# 1_0.net
KiCad netlist of a schematic drawn in Altium Designer
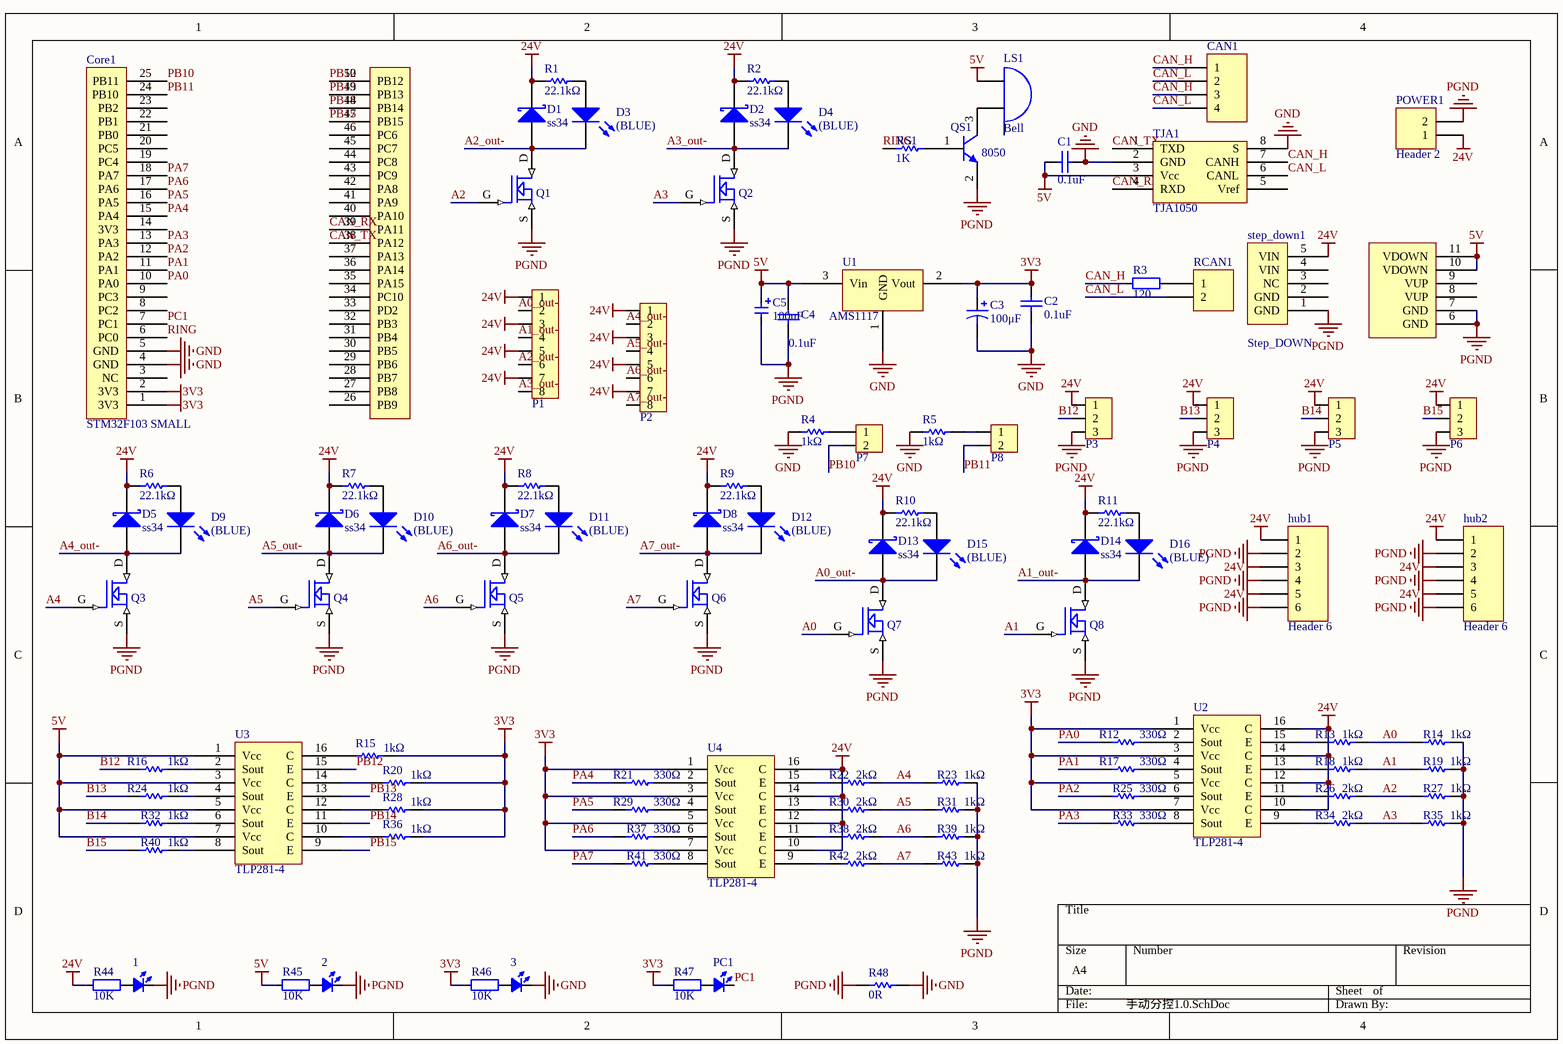
[diagram p0: 手动分控1.0.SchDoc]

(export (version "E")
  (design (tool "Eeschema 10.0.6"))
  (components
    (comp (ref "1")
      (value "LED_0603")
      (footprint "LED_0805_GREEN")
      (description "LED")
      (libsource (lib "Integrated_Library") (part "LED_0603"))
    )
    (comp (ref "2")
      (value "LED_0603")
      (footprint "LED_0805_GREEN")
      (description "LED")
      (libsource (lib "Integrated_Library") (part "LED_0603"))
    )
    (comp (ref "3")
      (value "LED_0603")
      (footprint "LED_0805_GREEN")
      (description "LED")
      (libsource (lib "Integrated_Library") (part "LED_0603"))
    )
    (comp (ref "C1")
      (value "0.1uF")
      (footprint "CAP-MLCC-0603")
      (description "Capacitor")
      (fields (field (name "Comment") "Cap") (field (name "PUBLISHER") "Altium Limited"))
      (libsource (lib "K60-mainboard-v3.1") (part "Cap"))
    )
    (comp (ref "C2")
      (value "0.1uF")
      (footprint "CAP-MLCC-0603")
      (description "Capacitor")
      (fields (field (name "Comment") "Cap") (field (name "PUBLISHER") "Altium Limited"))
      (libsource (lib "K60-mainboard-v3.1") (part "Cap"))
    )
    (comp (ref "C3")
      (value "100μF")
      (footprint "CAP-TAN-3216/CAPA")
      (description "钽电容")
      (fields (field (name "PUBLISHER") "Altium Limited"))
      (libsource (lib "Libraries_2014_0618") (part "CAP-TAN"))
    )
    (comp (ref "C4")
      (value "0.1uF")
      (footprint "CAP-MLCC-0603")
      (description "Capacitor")
      (fields (field (name "Comment") "Cap") (field (name "PUBLISHER") "Altium Limited"))
      (libsource (lib "K60-mainboard-v3.1") (part "Cap"))
    )
    (comp (ref "C5")
      (value "100uF")
      (footprint "CAP-TAN-6032/CAPC")
      (description "Capacitor")
      (fields (field (name "Comment") "Cap_Tan_0805"))
      (libsource (lib "Integrated_Library") (part "Cap_Tan_0805"))
    )
    (comp (ref "CAN1")
      (value "Header 4")
      (footprint "Green_4P")
      (description "Header, 4-Pin")
      (fields (field (name "PUBLISHER") "Altium Limited"))
      (libsource (lib "Libraries_2014_0618") (part "Header 4"))
    )
    (comp (ref "Core1")
      (value "STM32F103 SMALL")
      (footprint "STM32F103Small")
      (libsource (lib "K60-mainboard-v3.1") (part "STM32F103 SMALL"))
    )
    (comp (ref "D1")
      (value "ss34")
      (footprint "ss34")
      (description "肖特基二极管")
      (fields (field (name "PUBLISHER") "Altium Limited"))
      (libsource (lib "Libraries_2014_0618") (part "DIODE-Schottky"))
    )
    (comp (ref "D2")
      (value "ss34")
      (footprint "ss34")
      (description "肖特基二极管")
      (fields (field (name "PUBLISHER") "Altium Limited"))
      (libsource (lib "Libraries_2014_0618") (part "DIODE-Schottky"))
    )
    (comp (ref "D3")
      (value "(BLUE)")
      (footprint "LED-0805")
      (description "LED")
      (fields (field (name "PUBLISHER") "Altium Limited"))
      (libsource (lib "Libraries_2014_0618") (part "LED"))
    )
    (comp (ref "D4")
      (value "(BLUE)")
      (footprint "LED-0805")
      (description "LED")
      (fields (field (name "PUBLISHER") "Altium Limited"))
      (libsource (lib "Libraries_2014_0618") (part "LED"))
    )
    (comp (ref "D5")
      (value "ss34")
      (footprint "ss34")
      (description "肖特基二极管")
      (fields (field (name "PUBLISHER") "Altium Limited"))
      (libsource (lib "Libraries_2014_0618") (part "DIODE-Schottky"))
    )
    (comp (ref "D6")
      (value "ss34")
      (footprint "ss34")
      (description "肖特基二极管")
      (fields (field (name "PUBLISHER") "Altium Limited"))
      (libsource (lib "Libraries_2014_0618") (part "DIODE-Schottky"))
    )
    (comp (ref "D7")
      (value "ss34")
      (footprint "ss34")
      (description "肖特基二极管")
      (fields (field (name "PUBLISHER") "Altium Limited"))
      (libsource (lib "Libraries_2014_0618") (part "DIODE-Schottky"))
    )
    (comp (ref "D8")
      (value "ss34")
      (footprint "ss34")
      (description "肖特基二极管")
      (fields (field (name "PUBLISHER") "Altium Limited"))
      (libsource (lib "Libraries_2014_0618") (part "DIODE-Schottky"))
    )
    (comp (ref "D9")
      (value "(BLUE)")
      (footprint "LED-0805")
      (description "LED")
      (fields (field (name "PUBLISHER") "Altium Limited"))
      (libsource (lib "Libraries_2014_0618") (part "LED"))
    )
    (comp (ref "D10")
      (value "(BLUE)")
      (footprint "LED-0805")
      (description "LED")
      (fields (field (name "PUBLISHER") "Altium Limited"))
      (libsource (lib "Libraries_2014_0618") (part "LED"))
    )
    (comp (ref "D11")
      (value "(BLUE)")
      (footprint "LED-0805")
      (description "LED")
      (fields (field (name "PUBLISHER") "Altium Limited"))
      (libsource (lib "Libraries_2014_0618") (part "LED"))
    )
    (comp (ref "D12")
      (value "(BLUE)")
      (footprint "LED-0805")
      (description "LED")
      (fields (field (name "PUBLISHER") "Altium Limited"))
      (libsource (lib "Libraries_2014_0618") (part "LED"))
    )
    (comp (ref "D13")
      (value "ss34")
      (footprint "ss34")
      (description "肖特基二极管")
      (fields (field (name "PUBLISHER") "Altium Limited"))
      (libsource (lib "Libraries_2014_0618") (part "DIODE-Schottky"))
    )
    (comp (ref "D14")
      (value "ss34")
      (footprint "ss34")
      (description "肖特基二极管")
      (fields (field (name "PUBLISHER") "Altium Limited"))
      (libsource (lib "Libraries_2014_0618") (part "DIODE-Schottky"))
    )
    (comp (ref "D15")
      (value "(BLUE)")
      (footprint "LED-0805")
      (description "LED")
      (fields (field (name "PUBLISHER") "Altium Limited"))
      (libsource (lib "Libraries_2014_0618") (part "LED"))
    )
    (comp (ref "D16")
      (value "(BLUE)")
      (footprint "LED-0805")
      (description "LED")
      (fields (field (name "PUBLISHER") "Altium Limited"))
      (libsource (lib "Libraries_2014_0618") (part "LED"))
    )
    (comp (ref "hub1")
      (value "Header 6")
      (footprint "Green_6P")
      (description "Header, 6-Pin")
      (fields (field (name "PUBLISHER") "Altium Limited"))
      (libsource (lib "Libraries_2014_0618") (part "Header 6"))
    )
    (comp (ref "hub2")
      (value "Header 6")
      (footprint "Green_6P")
      (description "Header, 6-Pin")
      (fields (field (name "PUBLISHER") "Altium Limited"))
      (libsource (lib "Libraries_2014_0618") (part "Header 6"))
    )
    (comp (ref "LS1")
      (value "Bell")
      (footprint "CAP-ELE-PIN200/DIA250")
      (description "Electrical Bell")
      (fields (field (name "PUBLISHER") "Altium Limited"))
      (libsource (lib "Miscellaneous Devices") (part "Bell"))
    )
    (comp (ref "P1")
      (value "HDR1x8_1.27")
      (footprint "HDR1X8_1.27_180")
      (description "Header")
      (libsource (lib "Integrated_Library") (part "HDR1x8_1.27"))
    )
    (comp (ref "P2")
      (value "HDR1x8_1.27")
      (footprint "HDR1X8_1.27_180")
      (description "Header")
      (libsource (lib "Integrated_Library") (part "HDR1x8_1.27"))
    )
    (comp (ref "P3")
      (value "HDR1x3_2.54")
      (footprint "Green_3P")
      (description "Header")
      (libsource (lib "Integrated_Library") (part "HDR1x3_2.54"))
    )
    (comp (ref "P4")
      (value "HDR1x3_2.54")
      (footprint "Green_3P")
      (description "Header")
      (libsource (lib "Integrated_Library") (part "HDR1x3_2.54"))
    )
    (comp (ref "P5")
      (value "HDR1x3_2.54")
      (footprint "Green_3P")
      (description "Header")
      (libsource (lib "Integrated_Library") (part "HDR1x3_2.54"))
    )
    (comp (ref "P6")
      (value "HDR1x3_2.54")
      (footprint "Green_3P")
      (description "Header")
      (libsource (lib "Integrated_Library") (part "HDR1x3_2.54"))
    )
    (comp (ref "P7")
      (value "HDR1x2_2.54")
      (footprint "Green_2P")
      (description "Header")
      (libsource (lib "Integrated_Library") (part "HDR1x2_2.54"))
    )
    (comp (ref "P8")
      (value "HDR1x2_2.54")
      (footprint "Green_2P")
      (description "Header")
      (libsource (lib "Integrated_Library") (part "HDR1x2_2.54"))
    )
    (comp (ref "PC1")
      (value "LED_0603")
      (footprint "LED_0805_GREEN")
      (description "LED")
      (libsource (lib "Integrated_Library") (part "LED_0603"))
    )
    (comp (ref "POWER1")
      (value "Header 2")
      (footprint "Green_2P")
      (description "Header, 2-Pin")
      (fields (field (name "PUBLISHER") "Altium Limited"))
      (libsource (lib "K60-mainboard-v3.1") (part "Header 2"))
    )
    (comp (ref "Q1")
      (value "MOSFET N")
      (footprint "NMOS_SOT23")
      (description "IRF530")
      (libsource (lib "K60-mainboard-v3.1") (part "MOSFET N"))
    )
    (comp (ref "Q2")
      (value "MOSFET N")
      (footprint "NMOS_SOT23")
      (description "IRF530")
      (libsource (lib "K60-mainboard-v3.1") (part "MOSFET N"))
    )
    (comp (ref "Q3")
      (value "MOSFET N")
      (footprint "NMOS_SOT23")
      (description "IRF530")
      (libsource (lib "K60-mainboard-v3.1") (part "MOSFET N"))
    )
    (comp (ref "Q4")
      (value "MOSFET N")
      (footprint "NMOS_SOT23")
      (description "IRF530")
      (libsource (lib "K60-mainboard-v3.1") (part "MOSFET N"))
    )
    (comp (ref "Q5")
      (value "MOSFET N")
      (footprint "NMOS_SOT23")
      (description "IRF530")
      (libsource (lib "K60-mainboard-v3.1") (part "MOSFET N"))
    )
    (comp (ref "Q6")
      (value "MOSFET N")
      (footprint "NMOS_SOT23")
      (description "IRF530")
      (libsource (lib "K60-mainboard-v3.1") (part "MOSFET N"))
    )
    (comp (ref "Q7")
      (value "MOSFET N")
      (footprint "LR7843")
      (description "IRF530")
      (libsource (lib "K60-mainboard-v3.1") (part "MOSFET N"))
    )
    (comp (ref "Q8")
      (value "MOSFET N")
      (footprint "LR7843")
      (description "IRF530")
      (libsource (lib "K60-mainboard-v3.1") (part "MOSFET N"))
    )
    (comp (ref "QS1")
      (value "8050")
      (footprint "SOT-23B_N")
      (description "NPN Bipolar Transistor")
      (fields (field (name "PUBLISHER") "Altium Limited"))
      (libsource (lib "附加元件") (part "QNPN"))
    )
    (comp (ref "R1")
      (value "22.1kΩ")
      (footprint "RES-0603")
      (description "电阻")
      (fields (field (name "PUBLISHER") "Altium Limited"))
      (libsource (lib "Libraries_2014_0618") (part "RES"))
    )
    (comp (ref "R2")
      (value "22.1kΩ")
      (footprint "RES-0603")
      (description "电阻")
      (fields (field (name "PUBLISHER") "Altium Limited"))
      (libsource (lib "Libraries_2014_0618") (part "RES"))
    )
    (comp (ref "R3")
      (value "120")
      (footprint "RES-0603")
      (description "Resistor")
      (fields (field (name "Comment") "Res_0603"))
      (libsource (lib "Integrated_Library") (part "Res_0603"))
    )
    (comp (ref "R4")
      (value "1kΩ")
      (footprint "RES-0603")
      (description "电阻")
      (fields (field (name "PUBLISHER") "Altium Limited"))
      (libsource (lib "Libraries_2014_0618") (part "RES"))
    )
    (comp (ref "R5")
      (value "1kΩ")
      (footprint "RES-0603")
      (description "电阻")
      (fields (field (name "PUBLISHER") "Altium Limited"))
      (libsource (lib "Libraries_2014_0618") (part "RES"))
    )
    (comp (ref "R6")
      (value "22.1kΩ")
      (footprint "RES-0603")
      (description "电阻")
      (fields (field (name "PUBLISHER") "Altium Limited"))
      (libsource (lib "Libraries_2014_0618") (part "RES"))
    )
    (comp (ref "R7")
      (value "22.1kΩ")
      (footprint "RES-0603")
      (description "电阻")
      (fields (field (name "PUBLISHER") "Altium Limited"))
      (libsource (lib "Libraries_2014_0618") (part "RES"))
    )
    (comp (ref "R8")
      (value "22.1kΩ")
      (footprint "RES-0603")
      (description "电阻")
      (fields (field (name "PUBLISHER") "Altium Limited"))
      (libsource (lib "Libraries_2014_0618") (part "RES"))
    )
    (comp (ref "R9")
      (value "22.1kΩ")
      (footprint "RES-0603")
      (description "电阻")
      (fields (field (name "PUBLISHER") "Altium Limited"))
      (libsource (lib "Libraries_2014_0618") (part "RES"))
    )
    (comp (ref "R10")
      (value "22.1kΩ")
      (footprint "RES-0603")
      (description "电阻")
      (fields (field (name "PUBLISHER") "Altium Limited"))
      (libsource (lib "Libraries_2014_0618") (part "RES"))
    )
    (comp (ref "R11")
      (value "22.1kΩ")
      (footprint "RES-0603")
      (description "电阻")
      (fields (field (name "PUBLISHER") "Altium Limited"))
      (libsource (lib "Libraries_2014_0618") (part "RES"))
    )
    (comp (ref "R12")
      (value "330Ω")
      (footprint "RES-0603")
      (description "电阻")
      (fields (field (name "Comment") "RES") (field (name "PUBLISHER") "Altium Limited"))
      (libsource (lib "Libraries_2014_0215") (part "RES"))
    )
    (comp (ref "R13")
      (value "1kΩ")
      (footprint "RES-0603")
      (description "电阻")
      (fields (field (name "PUBLISHER") "Altium Limited"))
      (libsource (lib "Libraries_2014_0618") (part "RES"))
    )
    (comp (ref "R14")
      (value "1kΩ")
      (footprint "RES-0603")
      (description "电阻")
      (fields (field (name "PUBLISHER") "Altium Limited"))
      (libsource (lib "Libraries_2014_0618") (part "RES"))
    )
    (comp (ref "R15")
      (value "1kΩ")
      (footprint "RES-0603")
      (description "电阻")
      (fields (field (name "Comment") "RES") (field (name "PUBLISHER") "Altium Limited"))
      (libsource (lib "Libraries_2014_0215") (part "RES"))
    )
    (comp (ref "R16")
      (value "1kΩ")
      (footprint "RES-0603")
      (description "电阻")
      (fields (field (name "Comment") "RES") (field (name "PUBLISHER") "Altium Limited"))
      (libsource (lib "Libraries_2014_0215") (part "RES"))
    )
    (comp (ref "R17")
      (value "330Ω")
      (footprint "RES-0603")
      (description "电阻")
      (fields (field (name "Comment") "RES") (field (name "PUBLISHER") "Altium Limited"))
      (libsource (lib "Libraries_2014_0215") (part "RES"))
    )
    (comp (ref "R18")
      (value "1kΩ")
      (footprint "RES-0603")
      (description "电阻")
      (fields (field (name "PUBLISHER") "Altium Limited"))
      (libsource (lib "Libraries_2014_0618") (part "RES"))
    )
    (comp (ref "R19")
      (value "1kΩ")
      (footprint "RES-0603")
      (description "电阻")
      (fields (field (name "PUBLISHER") "Altium Limited"))
      (libsource (lib "Libraries_2014_0618") (part "RES"))
    )
    (comp (ref "R20")
      (value "1kΩ")
      (footprint "RES-0603")
      (description "电阻")
      (fields (field (name "Comment") "RES") (field (name "PUBLISHER") "Altium Limited"))
      (libsource (lib "Libraries_2014_0215") (part "RES"))
    )
    (comp (ref "R21")
      (value "330Ω")
      (footprint "RES-0603")
      (description "电阻")
      (fields (field (name "Comment") "RES") (field (name "PUBLISHER") "Altium Limited"))
      (libsource (lib "Libraries_2014_0215") (part "RES"))
    )
    (comp (ref "R22")
      (value "2kΩ")
      (footprint "RES-0603")
      (description "电阻")
      (fields (field (name "PUBLISHER") "Altium Limited"))
      (libsource (lib "Libraries_2014_0618") (part "RES"))
    )
    (comp (ref "R23")
      (value "1kΩ")
      (footprint "RES-0603")
      (description "电阻")
      (fields (field (name "PUBLISHER") "Altium Limited"))
      (libsource (lib "Libraries_2014_0618") (part "RES"))
    )
    (comp (ref "R24")
      (value "1kΩ")
      (footprint "RES-0603")
      (description "电阻")
      (fields (field (name "Comment") "RES") (field (name "PUBLISHER") "Altium Limited"))
      (libsource (lib "Libraries_2014_0215") (part "RES"))
    )
    (comp (ref "R25")
      (value "330Ω")
      (footprint "RES-0603")
      (description "电阻")
      (fields (field (name "PUBLISHER") "Altium Limited"))
      (libsource (lib "Libraries_2014_0618") (part "RES"))
    )
    (comp (ref "R26")
      (value "2kΩ")
      (footprint "RES-0603")
      (description "电阻")
      (fields (field (name "PUBLISHER") "Altium Limited"))
      (libsource (lib "Libraries_2014_0618") (part "RES"))
    )
    (comp (ref "R27")
      (value "1kΩ")
      (footprint "RES-0603")
      (description "电阻")
      (fields (field (name "PUBLISHER") "Altium Limited"))
      (libsource (lib "Libraries_2014_0618") (part "RES"))
    )
    (comp (ref "R28")
      (value "1kΩ")
      (footprint "RES-0603")
      (description "电阻")
      (fields (field (name "Comment") "RES") (field (name "PUBLISHER") "Altium Limited"))
      (libsource (lib "Libraries_2014_0215") (part "RES"))
    )
    (comp (ref "R29")
      (value "330Ω")
      (footprint "RES-0603")
      (description "电阻")
      (fields (field (name "Comment") "RES") (field (name "PUBLISHER") "Altium Limited"))
      (libsource (lib "Libraries_2014_0215") (part "RES"))
    )
    (comp (ref "R30")
      (value "2kΩ")
      (footprint "RES-0603")
      (description "电阻")
      (fields (field (name "PUBLISHER") "Altium Limited"))
      (libsource (lib "Libraries_2014_0618") (part "RES"))
    )
    (comp (ref "R31")
      (value "1kΩ")
      (footprint "RES-0603")
      (description "电阻")
      (fields (field (name "PUBLISHER") "Altium Limited"))
      (libsource (lib "Libraries_2014_0618") (part "RES"))
    )
    (comp (ref "R32")
      (value "1kΩ")
      (footprint "RES-0603")
      (description "电阻")
      (fields (field (name "PUBLISHER") "Altium Limited"))
      (libsource (lib "Libraries_2014_0618") (part "RES"))
    )
    (comp (ref "R33")
      (value "330Ω")
      (footprint "RES-0603")
      (description "电阻")
      (fields (field (name "PUBLISHER") "Altium Limited"))
      (libsource (lib "Libraries_2014_0618") (part "RES"))
    )
    (comp (ref "R34")
      (value "2kΩ")
      (footprint "RES-0603")
      (description "电阻")
      (fields (field (name "PUBLISHER") "Altium Limited"))
      (libsource (lib "Libraries_2014_0618") (part "RES"))
    )
    (comp (ref "R35")
      (value "1kΩ")
      (footprint "RES-0603")
      (description "电阻")
      (fields (field (name "PUBLISHER") "Altium Limited"))
      (libsource (lib "Libraries_2014_0618") (part "RES"))
    )
    (comp (ref "R36")
      (value "1kΩ")
      (footprint "RES-0603")
      (description "电阻")
      (fields (field (name "Comment") "RES") (field (name "PUBLISHER") "Altium Limited"))
      (libsource (lib "Libraries_2014_0215") (part "RES"))
    )
    (comp (ref "R37")
      (value "330Ω")
      (footprint "RES-0603")
      (description "电阻")
      (fields (field (name "PUBLISHER") "Altium Limited"))
      (libsource (lib "Libraries_2014_0618") (part "RES"))
    )
    (comp (ref "R38")
      (value "2kΩ")
      (footprint "RES-0603")
      (description "电阻")
      (fields (field (name "PUBLISHER") "Altium Limited"))
      (libsource (lib "Libraries_2014_0618") (part "RES"))
    )
    (comp (ref "R39")
      (value "1kΩ")
      (footprint "RES-0603")
      (description "电阻")
      (fields (field (name "PUBLISHER") "Altium Limited"))
      (libsource (lib "Libraries_2014_0618") (part "RES"))
    )
    (comp (ref "R40")
      (value "1kΩ")
      (footprint "RES-0603")
      (description "电阻")
      (fields (field (name "PUBLISHER") "Altium Limited"))
      (libsource (lib "Libraries_2014_0618") (part "RES"))
    )
    (comp (ref "R41")
      (value "330Ω")
      (footprint "RES-0603")
      (description "电阻")
      (fields (field (name "PUBLISHER") "Altium Limited"))
      (libsource (lib "Libraries_2014_0618") (part "RES"))
    )
    (comp (ref "R42")
      (value "2kΩ")
      (footprint "RES-0603")
      (description "电阻")
      (fields (field (name "PUBLISHER") "Altium Limited"))
      (libsource (lib "Libraries_2014_0618") (part "RES"))
    )
    (comp (ref "R43")
      (value "1kΩ")
      (footprint "RES-0603")
      (description "电阻")
      (fields (field (name "PUBLISHER") "Altium Limited"))
      (libsource (lib "Libraries_2014_0618") (part "RES"))
    )
    (comp (ref "R44")
      (value "10K")
      (footprint "RES-0603")
      (description "Resistor")
      (fields (field (name "Comment") "Res_0603"))
      (libsource (lib "Integrated_Library") (part "Res_0603"))
    )
    (comp (ref "R45")
      (value "10K")
      (footprint "RES-0603")
      (description "Resistor")
      (fields (field (name "Comment") "Res_0603"))
      (libsource (lib "Integrated_Library") (part "Res_0603"))
    )
    (comp (ref "R46")
      (value "10K")
      (footprint "RES-0603")
      (description "Resistor")
      (fields (field (name "Comment") "Res_0603"))
      (libsource (lib "Integrated_Library") (part "Res_0603"))
    )
    (comp (ref "R47")
      (value "10K")
      (footprint "RES-0603")
      (description "Resistor")
      (fields (field (name "Comment") "Res_0603"))
      (libsource (lib "Integrated_Library") (part "Res_0603"))
    )
    (comp (ref "R48")
      (value "0R")
      (footprint "RES-0603")
      (description "Resistor")
      (fields (field (name "Comment") "Res1") (field (name "PUBLISHER") "Altium Limited"))
      (libsource (lib "K60-mainboard-v3.1") (part "Res1"))
    )
    (comp (ref "RCAN1")
      (value "~")
      (footprint "HDR1X2")
      (description "Header, 2-Pin")
      (fields (field (name "PUBLISHER") "Altium Limited"))
      (libsource (lib "Miscellaneous Connectors") (part "Header 2"))
    )
    (comp (ref "RS1")
      (value "1K")
      (footprint "RES-0603")
      (description "Resistor")
      (fields (field (name "Comment") "Res1") (field (name "PUBLISHER") "Altium Limited"))
      (libsource (lib "K60-mainboard-v3.1") (part "Res1"))
    )
    (comp (ref "step_down1")
      (value "Step_DOWN")
      (footprint "Step_Up_Down")
      (libsource (lib "K60-mainboard-v3.1") (part "Step_DOWN"))
    )
    (comp (ref "TJA1")
      (value "TJA1050")
      (footprint "TJA1050")
      (description "CAN总线收发器")
      (libsource (lib "Libraries_2014_0618") (part "TJA1050"))
    )
    (comp (ref "U1") (value "AMS1117") (footprint "SOT223-3") (libsource (lib "AMS1117") (part "AMS１１１７")))
    (comp (ref "U2")
      (value "TLP281-4")
      (footprint "SOP16")
      (description "TLP521-4,TLP281-4")
      (libsource (lib "Libraries_2014_0215") (part "IC-TLP521-4"))
    )
    (comp (ref "U3")
      (value "TLP281-4")
      (footprint "SOP16")
      (description "TLP521-4,TLP281-4")
      (libsource (lib "Libraries_2014_0215") (part "IC-TLP521-4"))
    )
    (comp (ref "U4")
      (value "TLP281-4")
      (footprint "SOP16")
      (description "TLP521-4,TLP281-4")
      (libsource (lib "Libraries_2014_0215") (part "IC-TLP521-4"))
    )
  )
  (nets
    (net (code "1") (name "/A0") (class "Default")
      (node (ref "Q7") (pin "G") (pinfunction "G_G") (pintype "input"))
      (node (ref "R13") (pin "2") (pinfunction "2_2") (pintype "passive"))
      (node (ref "R14") (pin "2") (pinfunction "2_2") (pintype "passive"))
    )
    (net (code "2") (name "/A0_out-") (class "Default")
      (node (ref "D13") (pin "A") (pinfunction "A_A") (pintype "passive"))
      (node (ref "D15") (pin "2") (pinfunction "K_2") (pintype "passive"))
      (node (ref "P1") (pin "2") (pinfunction "2_2") (pintype "passive"))
      (node (ref "Q7") (pin "D") (pinfunction "D_D") (pintype "input"))
    )
    (net (code "3") (name "/A1") (class "Default")
      (node (ref "Q8") (pin "G") (pinfunction "G_G") (pintype "input"))
      (node (ref "R18") (pin "2") (pinfunction "2_2") (pintype "passive"))
      (node (ref "R19") (pin "2") (pinfunction "2_2") (pintype "passive"))
    )
    (net (code "4") (name "/A1_out-") (class "Default")
      (node (ref "D14") (pin "A") (pinfunction "A_A") (pintype "passive"))
      (node (ref "D16") (pin "2") (pinfunction "K_2") (pintype "passive"))
      (node (ref "P1") (pin "4") (pinfunction "4_4") (pintype "passive"))
      (node (ref "Q8") (pin "D") (pinfunction "D_D") (pintype "input"))
    )
    (net (code "5") (name "/A2") (class "Default")
      (node (ref "Q1") (pin "G") (pinfunction "G_G") (pintype "input"))
      (node (ref "R26") (pin "2") (pinfunction "2_2") (pintype "passive"))
      (node (ref "R27") (pin "2") (pinfunction "2_2") (pintype "passive"))
    )
    (net (code "6") (name "/A2_out-") (class "Default")
      (node (ref "D1") (pin "A") (pinfunction "A_A") (pintype "passive"))
      (node (ref "D3") (pin "2") (pinfunction "K_2") (pintype "passive"))
      (node (ref "P1") (pin "6") (pinfunction "6_6") (pintype "passive"))
      (node (ref "Q1") (pin "D") (pinfunction "D_D") (pintype "input"))
    )
    (net (code "7") (name "/A3") (class "Default")
      (node (ref "Q2") (pin "G") (pinfunction "G_G") (pintype "input"))
      (node (ref "R34") (pin "2") (pinfunction "2_2") (pintype "passive"))
      (node (ref "R35") (pin "2") (pinfunction "2_2") (pintype "passive"))
    )
    (net (code "8") (name "/A3_out-") (class "Default")
      (node (ref "D2") (pin "A") (pinfunction "A_A") (pintype "passive"))
      (node (ref "D4") (pin "2") (pinfunction "K_2") (pintype "passive"))
      (node (ref "P1") (pin "8") (pinfunction "8_8") (pintype "passive"))
      (node (ref "Q2") (pin "D") (pinfunction "D_D") (pintype "input"))
    )
    (net (code "9") (name "/A4") (class "Default")
      (node (ref "Q3") (pin "G") (pinfunction "G_G") (pintype "input"))
      (node (ref "R22") (pin "2") (pinfunction "2_2") (pintype "passive"))
      (node (ref "R23") (pin "2") (pinfunction "2_2") (pintype "passive"))
    )
    (net (code "10") (name "/A4_out-") (class "Default")
      (node (ref "D5") (pin "A") (pinfunction "A_A") (pintype "passive"))
      (node (ref "D9") (pin "2") (pinfunction "K_2") (pintype "passive"))
      (node (ref "P2") (pin "2") (pinfunction "2_2") (pintype "passive"))
      (node (ref "Q3") (pin "D") (pinfunction "D_D") (pintype "input"))
    )
    (net (code "11") (name "/A5") (class "Default")
      (node (ref "Q4") (pin "G") (pinfunction "G_G") (pintype "input"))
      (node (ref "R30") (pin "2") (pinfunction "2_2") (pintype "passive"))
      (node (ref "R31") (pin "2") (pinfunction "2_2") (pintype "passive"))
    )
    (net (code "12") (name "/A5_out-") (class "Default")
      (node (ref "D10") (pin "2") (pinfunction "K_2") (pintype "passive"))
      (node (ref "D6") (pin "A") (pinfunction "A_A") (pintype "passive"))
      (node (ref "P2") (pin "4") (pinfunction "4_4") (pintype "passive"))
      (node (ref "Q4") (pin "D") (pinfunction "D_D") (pintype "input"))
    )
    (net (code "13") (name "/A6") (class "Default")
      (node (ref "Q5") (pin "G") (pinfunction "G_G") (pintype "input"))
      (node (ref "R38") (pin "2") (pinfunction "2_2") (pintype "passive"))
      (node (ref "R39") (pin "2") (pinfunction "2_2") (pintype "passive"))
    )
    (net (code "14") (name "/A6_out-") (class "Default")
      (node (ref "D11") (pin "2") (pinfunction "K_2") (pintype "passive"))
      (node (ref "D7") (pin "A") (pinfunction "A_A") (pintype "passive"))
      (node (ref "P2") (pin "6") (pinfunction "6_6") (pintype "passive"))
      (node (ref "Q5") (pin "D") (pinfunction "D_D") (pintype "input"))
    )
    (net (code "15") (name "/A7") (class "Default")
      (node (ref "Q6") (pin "G") (pinfunction "G_G") (pintype "input"))
      (node (ref "R42") (pin "2") (pinfunction "2_2") (pintype "passive"))
      (node (ref "R43") (pin "2") (pinfunction "2_2") (pintype "passive"))
    )
    (net (code "16") (name "/A7_out-") (class "Default")
      (node (ref "D12") (pin "2") (pinfunction "K_2") (pintype "passive"))
      (node (ref "D8") (pin "A") (pinfunction "A_A") (pintype "passive"))
      (node (ref "P2") (pin "8") (pinfunction "8_8") (pintype "passive"))
      (node (ref "Q6") (pin "D") (pinfunction "D_D") (pintype "input"))
    )
    (net (code "17") (name "/B12") (class "Default")
      (node (ref "P3") (pin "2") (pinfunction "2_2") (pintype "passive"))
      (node (ref "R16") (pin "1") (pinfunction "1_1") (pintype "passive"))
    )
    (net (code "18") (name "/B13") (class "Default")
      (node (ref "P4") (pin "2") (pinfunction "2_2") (pintype "passive"))
      (node (ref "R24") (pin "1") (pinfunction "1_1") (pintype "passive"))
    )
    (net (code "19") (name "/B14") (class "Default")
      (node (ref "P5") (pin "2") (pinfunction "2_2") (pintype "passive"))
      (node (ref "R32") (pin "1") (pinfunction "1_1") (pintype "passive"))
    )
    (net (code "20") (name "/B15") (class "Default")
      (node (ref "P6") (pin "2") (pinfunction "2_2") (pintype "passive"))
      (node (ref "R40") (pin "1") (pinfunction "1_1") (pintype "passive"))
    )
    (net (code "21") (name "/CAN_H") (class "Default")
      (node (ref "CAN1") (pin "1") (pinfunction "1_1") (pintype "passive"))
      (node (ref "CAN1") (pin "3") (pinfunction "3_3") (pintype "passive"))
      (node (ref "R3") (pin "2") (pinfunction "2_2") (pintype "passive"))
      (node (ref "TJA1") (pin "7") (pinfunction "CANH_7") (pintype "passive"))
    )
    (net (code "22") (name "/CAN_L") (class "Default")
      (node (ref "CAN1") (pin "2") (pinfunction "2_2") (pintype "passive"))
      (node (ref "CAN1") (pin "4") (pinfunction "4_4") (pintype "passive"))
      (node (ref "RCAN1") (pin "2") (pinfunction "2_2") (pintype "passive"))
      (node (ref "TJA1") (pin "6") (pinfunction "CANL_6") (pintype "passive"))
    )
    (net (code "23") (name "/CAN_RX") (class "Default")
      (node (ref "Core1") (pin "39") (pinfunction "PA11_39") (pintype "passive"))
      (node (ref "TJA1") (pin "4") (pinfunction "RXD_4") (pintype "passive"))
    )
    (net (code "24") (name "/CAN_TX") (class "Default")
      (node (ref "Core1") (pin "38") (pinfunction "PA12_38") (pintype "passive"))
      (node (ref "TJA1") (pin "1") (pinfunction "TXD_1") (pintype "passive"))
    )
    (net (code "25") (name "/PA0") (class "Default")
      (node (ref "Core1") (pin "10") (pinfunction "PA0_10") (pintype "passive"))
      (node (ref "R12") (pin "1") (pinfunction "1_1") (pintype "passive"))
    )
    (net (code "26") (name "/PA1") (class "Default")
      (node (ref "Core1") (pin "11") (pinfunction "PA1_11") (pintype "passive"))
      (node (ref "R17") (pin "1") (pinfunction "1_1") (pintype "passive"))
    )
    (net (code "27") (name "/PA2") (class "Default")
      (node (ref "Core1") (pin "12") (pinfunction "PA2_12") (pintype "passive"))
      (node (ref "R25") (pin "1") (pinfunction "1_1") (pintype "passive"))
    )
    (net (code "28") (name "/PA3") (class "Default")
      (node (ref "Core1") (pin "13") (pinfunction "PA3_13") (pintype "passive"))
      (node (ref "R33") (pin "1") (pinfunction "1_1") (pintype "passive"))
    )
    (net (code "29") (name "/PA4") (class "Default")
      (node (ref "Core1") (pin "15") (pinfunction "PA4_15") (pintype "passive"))
      (node (ref "R21") (pin "1") (pinfunction "1_1") (pintype "passive"))
    )
    (net (code "30") (name "/PA5") (class "Default")
      (node (ref "Core1") (pin "16") (pinfunction "PA5_16") (pintype "passive"))
      (node (ref "R29") (pin "1") (pinfunction "1_1") (pintype "passive"))
    )
    (net (code "31") (name "/PA6") (class "Default")
      (node (ref "Core1") (pin "17") (pinfunction "PA6_17") (pintype "passive"))
      (node (ref "R37") (pin "1") (pinfunction "1_1") (pintype "passive"))
    )
    (net (code "32") (name "/PA7") (class "Default")
      (node (ref "Core1") (pin "18") (pinfunction "PA7_18") (pintype "passive"))
      (node (ref "R41") (pin "1") (pinfunction "1_1") (pintype "passive"))
    )
    (net (code "33") (name "/PB10") (class "Default")
      (node (ref "Core1") (pin "25") (pinfunction "PB11_25") (pintype "passive"))
      (node (ref "P7") (pin "2") (pinfunction "2_2") (pintype "passive"))
    )
    (net (code "34") (name "/PB11") (class "Default")
      (node (ref "Core1") (pin "24") (pinfunction "PB10_24") (pintype "passive"))
      (node (ref "P8") (pin "2") (pinfunction "2_2") (pintype "passive"))
    )
    (net (code "35") (name "/PB12") (class "Default")
      (node (ref "Core1") (pin "50") (pinfunction "PB12_50") (pintype "passive"))
      (node (ref "U3") (pin "15") (pinfunction "E_15") (pintype "power_in"))
    )
    (net (code "36") (name "/PB13") (class "Default")
      (node (ref "Core1") (pin "49") (pinfunction "PB13_49") (pintype "passive"))
      (node (ref "U3") (pin "13") (pinfunction "E_13") (pintype "power_in"))
    )
    (net (code "37") (name "/PB14") (class "Default")
      (node (ref "Core1") (pin "48") (pinfunction "PB14_48") (pintype "passive"))
      (node (ref "U3") (pin "11") (pinfunction "E_11") (pintype "power_in"))
    )
    (net (code "38") (name "/PB15") (class "Default")
      (node (ref "Core1") (pin "47") (pinfunction "PB15_47") (pintype "passive"))
      (node (ref "U3") (pin "9") (pinfunction "E_9") (pintype "power_in"))
    )
    (net (code "39") (name "/PC1") (class "Default")
      (node (ref "Core1") (pin "7") (pinfunction "PC1_7") (pintype "passive"))
      (node (ref "PC1") (pin "2") (pinfunction "K_2") (pintype "passive"))
    )
    (net (code "40") (name "/RING") (class "Default")
      (node (ref "Core1") (pin "6") (pinfunction "PC0_6") (pintype "passive"))
      (node (ref "RS1") (pin "2") (pinfunction "2_2") (pintype "passive"))
    )
    (net (code "41") (name "3V3") (class "Default")
      (node (ref "C2") (pin "2") (pinfunction "2_2") (pintype "passive"))
      (node (ref "C3") (pin "1") (pinfunction "1_1") (pintype "passive"))
      (node (ref "Core1") (pin "1") (pinfunction "3V3_1") (pintype "passive"))
      (node (ref "Core1") (pin "2") (pinfunction "3V3_2") (pintype "passive"))
      (node (ref "R15") (pin "2") (pinfunction "2_2") (pintype "passive"))
      (node (ref "R20") (pin "2") (pinfunction "2_2") (pintype "passive"))
      (node (ref "R28") (pin "2") (pinfunction "2_2") (pintype "passive"))
      (node (ref "R36") (pin "2") (pinfunction "2_2") (pintype "passive"))
      (node (ref "R46") (pin "2") (pinfunction "2_2") (pintype "passive"))
      (node (ref "R47") (pin "2") (pinfunction "2_2") (pintype "passive"))
      (node (ref "U1") (pin "2") (pinfunction "Vout_2") (pintype "passive"))
      (node (ref "U2") (pin "1") (pinfunction "Vcc_1") (pintype "power_in"))
      (node (ref "U2") (pin "3") (pinfunction "Vcc_3") (pintype "power_in"))
      (node (ref "U2") (pin "5") (pinfunction "Vcc_5") (pintype "power_in"))
      (node (ref "U2") (pin "7") (pinfunction "Vcc_7") (pintype "power_in"))
      (node (ref "U4") (pin "1") (pinfunction "Vcc_1") (pintype "power_in"))
      (node (ref "U4") (pin "3") (pinfunction "Vcc_3") (pintype "power_in"))
      (node (ref "U4") (pin "5") (pinfunction "Vcc_5") (pintype "power_in"))
      (node (ref "U4") (pin "7") (pinfunction "Vcc_7") (pintype "power_in"))
    )
    (net (code "42") (name "5V") (class "Default")
      (node (ref "C1") (pin "1") (pinfunction "1_1") (pintype "passive"))
      (node (ref "C4") (pin "2") (pinfunction "2_2") (pintype "passive"))
      (node (ref "C5") (pin "1") (pinfunction "1_1") (pintype "passive"))
      (node (ref "LS1") (pin "1") (pinfunction "A_1") (pintype "passive"))
      (node (ref "R45") (pin "2") (pinfunction "2_2") (pintype "passive"))
      (node (ref "TJA1") (pin "3") (pinfunction "Vcc_3") (pintype "passive"))
      (node (ref "U1") (pin "3") (pinfunction "Vin_3") (pintype "passive"))
      (node (ref "U3") (pin "1") (pinfunction "Vcc_1") (pintype "power_in"))
      (node (ref "U3") (pin "3") (pinfunction "Vcc_3") (pintype "power_in"))
      (node (ref "U3") (pin "5") (pinfunction "Vcc_5") (pintype "power_in"))
      (node (ref "U3") (pin "7") (pinfunction "Vcc_7") (pintype "power_in"))
      (node (ref "step_down1") (pin "10") (pinfunction "VDOWN_10") (pintype "passive"))
      (node (ref "step_down1") (pin "11") (pinfunction "VDOWN_11") (pintype "passive"))
    )
    (net (code "43") (name "24V") (class "Default")
      (node (ref "D1") (pin "K") (pinfunction "K_K") (pintype "passive"))
      (node (ref "D13") (pin "K") (pinfunction "K_K") (pintype "passive"))
      (node (ref "D14") (pin "K") (pinfunction "K_K") (pintype "passive"))
      (node (ref "D2") (pin "K") (pinfunction "K_K") (pintype "passive"))
      (node (ref "D5") (pin "K") (pinfunction "K_K") (pintype "passive"))
      (node (ref "D6") (pin "K") (pinfunction "K_K") (pintype "passive"))
      (node (ref "D7") (pin "K") (pinfunction "K_K") (pintype "passive"))
      (node (ref "D8") (pin "K") (pinfunction "K_K") (pintype "passive"))
      (node (ref "P1") (pin "1") (pinfunction "1_1") (pintype "passive"))
      (node (ref "P1") (pin "3") (pinfunction "3_3") (pintype "passive"))
      (node (ref "P1") (pin "5") (pinfunction "5_5") (pintype "passive"))
      (node (ref "P1") (pin "7") (pinfunction "7_7") (pintype "passive"))
      (node (ref "P2") (pin "1") (pinfunction "1_1") (pintype "passive"))
      (node (ref "P2") (pin "3") (pinfunction "3_3") (pintype "passive"))
      (node (ref "P2") (pin "5") (pinfunction "5_5") (pintype "passive"))
      (node (ref "P2") (pin "7") (pinfunction "7_7") (pintype "passive"))
      (node (ref "P3") (pin "1") (pinfunction "1_1") (pintype "passive"))
      (node (ref "P4") (pin "1") (pinfunction "1_1") (pintype "passive"))
      (node (ref "P5") (pin "1") (pinfunction "1_1") (pintype "passive"))
      (node (ref "P6") (pin "1") (pinfunction "1_1") (pintype "passive"))
      (node (ref "POWER1") (pin "1") (pinfunction "1_1") (pintype "passive"))
      (node (ref "R1") (pin "2") (pinfunction "2_2") (pintype "passive"))
      (node (ref "R10") (pin "2") (pinfunction "2_2") (pintype "passive"))
      (node (ref "R11") (pin "1") (pinfunction "1_1") (pintype "passive"))
      (node (ref "R2") (pin "1") (pinfunction "1_1") (pintype "passive"))
      (node (ref "R44") (pin "2") (pinfunction "2_2") (pintype "passive"))
      (node (ref "R6") (pin "2") (pinfunction "2_2") (pintype "passive"))
      (node (ref "R7") (pin "1") (pinfunction "1_1") (pintype "passive"))
      (node (ref "R8") (pin "2") (pinfunction "2_2") (pintype "passive"))
      (node (ref "R9") (pin "1") (pinfunction "1_1") (pintype "passive"))
      (node (ref "U2") (pin "10") (pinfunction "C_10") (pintype "power_in"))
      (node (ref "U2") (pin "12") (pinfunction "C_12") (pintype "power_in"))
      (node (ref "U2") (pin "14") (pinfunction "C_14") (pintype "power_in"))
      (node (ref "U2") (pin "16") (pinfunction "C_16") (pintype "power_in"))
      (node (ref "U4") (pin "10") (pinfunction "C_10") (pintype "power_in"))
      (node (ref "U4") (pin "12") (pinfunction "C_12") (pintype "power_in"))
      (node (ref "U4") (pin "14") (pinfunction "C_14") (pintype "power_in"))
      (node (ref "U4") (pin "16") (pinfunction "C_16") (pintype "power_in"))
      (node (ref "hub1") (pin "1") (pinfunction "1_1") (pintype "passive"))
      (node (ref "hub1") (pin "3") (pinfunction "3_3") (pintype "passive"))
      (node (ref "hub1") (pin "5") (pinfunction "5_5") (pintype "passive"))
      (node (ref "hub2") (pin "1") (pinfunction "1_1") (pintype "passive"))
      (node (ref "hub2") (pin "3") (pinfunction "3_3") (pintype "passive"))
      (node (ref "hub2") (pin "5") (pinfunction "5_5") (pintype "passive"))
      (node (ref "step_down1") (pin "5") (pinfunction "VIN_5") (pintype "passive"))
    )
    (net (code "44") (name "GND") (class "Default")
      (node (ref "3") (pin "2") (pinfunction "K_2") (pintype "passive"))
      (node (ref "C1") (pin "2") (pinfunction "2_2") (pintype "passive"))
      (node (ref "C2") (pin "1") (pinfunction "1_1") (pintype "passive"))
      (node (ref "C3") (pin "2") (pinfunction "2_2") (pintype "passive"))
      (node (ref "Core1") (pin "4") (pinfunction "GND_4") (pintype "passive"))
      (node (ref "Core1") (pin "5") (pinfunction "GND_5") (pintype "passive"))
      (node (ref "R4") (pin "1") (pinfunction "1_1") (pintype "passive"))
      (node (ref "R48") (pin "1") (pinfunction "1_1") (pintype "passive"))
      (node (ref "R5") (pin "1") (pinfunction "1_1") (pintype "passive"))
      (node (ref "TJA1") (pin "2") (pinfunction "GND_2") (pintype "passive"))
      (node (ref "TJA1") (pin "8") (pinfunction "S_8") (pintype "passive"))
      (node (ref "U1") (pin "1") (pinfunction "GND_1") (pintype "passive"))
    )
    (net (code "45") (name "Net-(1-A)") (class "Default")
      (node (ref "1") (pin "1") (pinfunction "A_1") (pintype "passive"))
      (node (ref "R44") (pin "1") (pinfunction "1_1") (pintype "passive"))
    )
    (net (code "46") (name "Net-(2-A)") (class "Default")
      (node (ref "2") (pin "1") (pinfunction "A_1") (pintype "passive"))
      (node (ref "R45") (pin "1") (pinfunction "1_1") (pintype "passive"))
    )
    (net (code "47") (name "Net-(3-A)") (class "Default")
      (node (ref "3") (pin "1") (pinfunction "A_1") (pintype "passive"))
      (node (ref "R46") (pin "1") (pinfunction "1_1") (pintype "passive"))
    )
    (net (code "48") (name "Net-(D3-A)") (class "Default")
      (node (ref "D3") (pin "1") (pinfunction "A_1") (pintype "passive"))
      (node (ref "R1") (pin "1") (pinfunction "1_1") (pintype "passive"))
    )
    (net (code "49") (name "Net-(D4-A)") (class "Default")
      (node (ref "D4") (pin "1") (pinfunction "A_1") (pintype "passive"))
      (node (ref "R2") (pin "2") (pinfunction "2_2") (pintype "passive"))
    )
    (net (code "50") (name "Net-(D9-A)") (class "Default")
      (node (ref "D9") (pin "1") (pinfunction "A_1") (pintype "passive"))
      (node (ref "R6") (pin "1") (pinfunction "1_1") (pintype "passive"))
    )
    (net (code "51") (name "Net-(D10-A)") (class "Default")
      (node (ref "D10") (pin "1") (pinfunction "A_1") (pintype "passive"))
      (node (ref "R7") (pin "2") (pinfunction "2_2") (pintype "passive"))
    )
    (net (code "52") (name "Net-(D11-A)") (class "Default")
      (node (ref "D11") (pin "1") (pinfunction "A_1") (pintype "passive"))
      (node (ref "R8") (pin "1") (pinfunction "1_1") (pintype "passive"))
    )
    (net (code "53") (name "Net-(D12-A)") (class "Default")
      (node (ref "D12") (pin "1") (pinfunction "A_1") (pintype "passive"))
      (node (ref "R9") (pin "2") (pinfunction "2_2") (pintype "passive"))
    )
    (net (code "54") (name "Net-(D15-A)") (class "Default")
      (node (ref "D15") (pin "1") (pinfunction "A_1") (pintype "passive"))
      (node (ref "R10") (pin "1") (pinfunction "1_1") (pintype "passive"))
    )
    (net (code "55") (name "Net-(D16-A)") (class "Default")
      (node (ref "D16") (pin "1") (pinfunction "A_1") (pintype "passive"))
      (node (ref "R11") (pin "2") (pinfunction "2_2") (pintype "passive"))
    )
    (net (code "56") (name "Net-(LS1-B)") (class "Default")
      (node (ref "LS1") (pin "2") (pinfunction "B_2") (pintype "passive"))
      (node (ref "QS1") (pin "3") (pinfunction "C_3") (pintype "passive"))
    )
    (net (code "57") (name "Net-(P7-Pad1)") (class "Default")
      (node (ref "P7") (pin "1") (pinfunction "1_1") (pintype "passive"))
      (node (ref "R4") (pin "2") (pinfunction "2_2") (pintype "passive"))
    )
    (net (code "58") (name "Net-(P8-Pad1)") (class "Default")
      (node (ref "P8") (pin "1") (pinfunction "1_1") (pintype "passive"))
      (node (ref "R5") (pin "2") (pinfunction "2_2") (pintype "passive"))
    )
    (net (code "59") (name "Net-(PC1-A)") (class "Default")
      (node (ref "PC1") (pin "1") (pinfunction "A_1") (pintype "passive"))
      (node (ref "R47") (pin "1") (pinfunction "1_1") (pintype "passive"))
    )
    (net (code "60") (name "Net-(QS1-B)") (class "Default")
      (node (ref "QS1") (pin "1") (pinfunction "B_1") (pintype "passive"))
      (node (ref "RS1") (pin "1") (pinfunction "1_1") (pintype "passive"))
    )
    (net (code "61") (name "Net-(R3-Pad1)") (class "Default")
      (node (ref "R3") (pin "1") (pinfunction "1_1") (pintype "passive"))
      (node (ref "RCAN1") (pin "1") (pinfunction "1_1") (pintype "passive"))
    )
    (net (code "62") (name "Net-(R12-Pad2)") (class "Default")
      (node (ref "R12") (pin "2") (pinfunction "2_2") (pintype "passive"))
      (node (ref "U2") (pin "2") (pinfunction "Sout_2") (pintype "power_in"))
    )
    (net (code "63") (name "Net-(R13-Pad1)") (class "Default")
      (node (ref "R13") (pin "1") (pinfunction "1_1") (pintype "passive"))
      (node (ref "U2") (pin "15") (pinfunction "E_15") (pintype "power_in"))
    )
    (net (code "64") (name "Net-(R15-Pad1)") (class "Default")
      (node (ref "R15") (pin "1") (pinfunction "1_1") (pintype "passive"))
      (node (ref "U3") (pin "16") (pinfunction "C_16") (pintype "power_in"))
    )
    (net (code "65") (name "Net-(R16-Pad2)") (class "Default")
      (node (ref "R16") (pin "2") (pinfunction "2_2") (pintype "passive"))
      (node (ref "U3") (pin "2") (pinfunction "Sout_2") (pintype "power_in"))
    )
    (net (code "66") (name "Net-(R17-Pad2)") (class "Default")
      (node (ref "R17") (pin "2") (pinfunction "2_2") (pintype "passive"))
      (node (ref "U2") (pin "4") (pinfunction "Sout_4") (pintype "power_in"))
    )
    (net (code "67") (name "Net-(R18-Pad1)") (class "Default")
      (node (ref "R18") (pin "1") (pinfunction "1_1") (pintype "passive"))
      (node (ref "U2") (pin "13") (pinfunction "E_13") (pintype "power_in"))
    )
    (net (code "68") (name "Net-(R20-Pad1)") (class "Default")
      (node (ref "R20") (pin "1") (pinfunction "1_1") (pintype "passive"))
      (node (ref "U3") (pin "14") (pinfunction "C_14") (pintype "power_in"))
    )
    (net (code "69") (name "Net-(R21-Pad2)") (class "Default")
      (node (ref "R21") (pin "2") (pinfunction "2_2") (pintype "passive"))
      (node (ref "U4") (pin "2") (pinfunction "Sout_2") (pintype "power_in"))
    )
    (net (code "70") (name "Net-(R22-Pad1)") (class "Default")
      (node (ref "R22") (pin "1") (pinfunction "1_1") (pintype "passive"))
      (node (ref "U4") (pin "15") (pinfunction "E_15") (pintype "power_in"))
    )
    (net (code "71") (name "Net-(R24-Pad2)") (class "Default")
      (node (ref "R24") (pin "2") (pinfunction "2_2") (pintype "passive"))
      (node (ref "U3") (pin "4") (pinfunction "Sout_4") (pintype "power_in"))
    )
    (net (code "72") (name "Net-(R25-Pad2)") (class "Default")
      (node (ref "R25") (pin "2") (pinfunction "2_2") (pintype "passive"))
      (node (ref "U2") (pin "6") (pinfunction "Sout_6") (pintype "power_in"))
    )
    (net (code "73") (name "Net-(R26-Pad1)") (class "Default")
      (node (ref "R26") (pin "1") (pinfunction "1_1") (pintype "passive"))
      (node (ref "U2") (pin "11") (pinfunction "E_11") (pintype "power_in"))
    )
    (net (code "74") (name "Net-(R28-Pad1)") (class "Default")
      (node (ref "R28") (pin "1") (pinfunction "1_1") (pintype "passive"))
      (node (ref "U3") (pin "12") (pinfunction "C_12") (pintype "power_in"))
    )
    (net (code "75") (name "Net-(R29-Pad2)") (class "Default")
      (node (ref "R29") (pin "2") (pinfunction "2_2") (pintype "passive"))
      (node (ref "U4") (pin "4") (pinfunction "Sout_4") (pintype "power_in"))
    )
    (net (code "76") (name "Net-(R30-Pad1)") (class "Default")
      (node (ref "R30") (pin "1") (pinfunction "1_1") (pintype "passive"))
      (node (ref "U4") (pin "13") (pinfunction "E_13") (pintype "power_in"))
    )
    (net (code "77") (name "Net-(R32-Pad2)") (class "Default")
      (node (ref "R32") (pin "2") (pinfunction "2_2") (pintype "passive"))
      (node (ref "U3") (pin "6") (pinfunction "Sout_6") (pintype "power_in"))
    )
    (net (code "78") (name "Net-(R33-Pad2)") (class "Default")
      (node (ref "R33") (pin "2") (pinfunction "2_2") (pintype "passive"))
      (node (ref "U2") (pin "8") (pinfunction "Sout_8") (pintype "power_in"))
    )
    (net (code "79") (name "Net-(R34-Pad1)") (class "Default")
      (node (ref "R34") (pin "1") (pinfunction "1_1") (pintype "passive"))
      (node (ref "U2") (pin "9") (pinfunction "E_9") (pintype "power_in"))
    )
    (net (code "80") (name "Net-(R36-Pad1)") (class "Default")
      (node (ref "R36") (pin "1") (pinfunction "1_1") (pintype "passive"))
      (node (ref "U3") (pin "10") (pinfunction "C_10") (pintype "power_in"))
    )
    (net (code "81") (name "Net-(R37-Pad2)") (class "Default")
      (node (ref "R37") (pin "2") (pinfunction "2_2") (pintype "passive"))
      (node (ref "U4") (pin "6") (pinfunction "Sout_6") (pintype "power_in"))
    )
    (net (code "82") (name "Net-(R38-Pad1)") (class "Default")
      (node (ref "R38") (pin "1") (pinfunction "1_1") (pintype "passive"))
      (node (ref "U4") (pin "11") (pinfunction "E_11") (pintype "power_in"))
    )
    (net (code "83") (name "Net-(R40-Pad2)") (class "Default")
      (node (ref "R40") (pin "2") (pinfunction "2_2") (pintype "passive"))
      (node (ref "U3") (pin "8") (pinfunction "Sout_8") (pintype "power_in"))
    )
    (net (code "84") (name "Net-(R41-Pad2)") (class "Default")
      (node (ref "R41") (pin "2") (pinfunction "2_2") (pintype "passive"))
      (node (ref "U4") (pin "8") (pinfunction "Sout_8") (pintype "power_in"))
    )
    (net (code "85") (name "Net-(R42-Pad1)") (class "Default")
      (node (ref "R42") (pin "1") (pinfunction "1_1") (pintype "passive"))
      (node (ref "U4") (pin "9") (pinfunction "E_9") (pintype "power_in"))
    )
    (net (code "86") (name "PGND") (class "Default")
      (node (ref "1") (pin "2") (pinfunction "K_2") (pintype "passive"))
      (node (ref "2") (pin "2") (pinfunction "K_2") (pintype "passive"))
      (node (ref "C4") (pin "1") (pinfunction "1_1") (pintype "passive"))
      (node (ref "C5") (pin "2") (pinfunction "2_2") (pintype "passive"))
      (node (ref "P3") (pin "3") (pinfunction "3_3") (pintype "passive"))
      (node (ref "P4") (pin "3") (pinfunction "3_3") (pintype "passive"))
      (node (ref "P5") (pin "3") (pinfunction "3_3") (pintype "passive"))
      (node (ref "P6") (pin "3") (pinfunction "3_3") (pintype "passive"))
      (node (ref "POWER1") (pin "2") (pinfunction "2_2") (pintype "passive"))
      (node (ref "Q1") (pin "S") (pinfunction "S_S") (pintype "input"))
      (node (ref "Q2") (pin "S") (pinfunction "S_S") (pintype "input"))
      (node (ref "Q3") (pin "S") (pinfunction "S_S") (pintype "input"))
      (node (ref "Q4") (pin "S") (pinfunction "S_S") (pintype "input"))
      (node (ref "Q5") (pin "S") (pinfunction "S_S") (pintype "input"))
      (node (ref "Q6") (pin "S") (pinfunction "S_S") (pintype "input"))
      (node (ref "Q7") (pin "S") (pinfunction "S_S") (pintype "input"))
      (node (ref "Q8") (pin "S") (pinfunction "S_S") (pintype "input"))
      (node (ref "QS1") (pin "2") (pinfunction "E_2") (pintype "passive"))
      (node (ref "R14") (pin "1") (pinfunction "1_1") (pintype "passive"))
      (node (ref "R19") (pin "1") (pinfunction "1_1") (pintype "passive"))
      (node (ref "R23") (pin "1") (pinfunction "1_1") (pintype "passive"))
      (node (ref "R27") (pin "1") (pinfunction "1_1") (pintype "passive"))
      (node (ref "R31") (pin "1") (pinfunction "1_1") (pintype "passive"))
      (node (ref "R35") (pin "1") (pinfunction "1_1") (pintype "passive"))
      (node (ref "R39") (pin "1") (pinfunction "1_1") (pintype "passive"))
      (node (ref "R43") (pin "1") (pinfunction "1_1") (pintype "passive"))
      (node (ref "R48") (pin "2") (pinfunction "2_2") (pintype "passive"))
      (node (ref "hub1") (pin "2") (pinfunction "2_2") (pintype "passive"))
      (node (ref "hub1") (pin "4") (pinfunction "4_4") (pintype "passive"))
      (node (ref "hub1") (pin "6") (pinfunction "6_6") (pintype "passive"))
      (node (ref "hub2") (pin "2") (pinfunction "2_2") (pintype "passive"))
      (node (ref "hub2") (pin "4") (pinfunction "4_4") (pintype "passive"))
      (node (ref "hub2") (pin "6") (pinfunction "6_6") (pintype "passive"))
      (node (ref "step_down1") (pin "1") (pinfunction "GND_1") (pintype "passive"))
      (node (ref "step_down1") (pin "6") (pinfunction "GND_6") (pintype "passive"))
      (node (ref "step_down1") (pin "7") (pinfunction "GND_7") (pintype "passive"))
    )
    (net (code "87") (name "unconnected-(Core1-3V3-Pad14)") (class "Default")
      (node (ref "Core1") (pin "14") (pinfunction "3V3_14") (pintype "passive"))
    )
    (net (code "88") (name "unconnected-(Core1-NC-Pad3)") (class "Default")
      (node (ref "Core1") (pin "3") (pinfunction "NC_3") (pintype "passive"))
    )
    (net (code "89") (name "unconnected-(Core1-PA8-Pad42)") (class "Default")
      (node (ref "Core1") (pin "42") (pinfunction "PA8_42") (pintype "passive"))
    )
    (net (code "90") (name "unconnected-(Core1-PA9-Pad41)") (class "Default")
      (node (ref "Core1") (pin "41") (pinfunction "PA9_41") (pintype "passive"))
    )
    (net (code "91") (name "unconnected-(Core1-PA10-Pad40)") (class "Default")
      (node (ref "Core1") (pin "40") (pinfunction "PA10_40") (pintype "passive"))
    )
    (net (code "92") (name "unconnected-(Core1-PA13-Pad37)") (class "Default")
      (node (ref "Core1") (pin "37") (pinfunction "PA13_37") (pintype "passive"))
    )
    (net (code "93") (name "unconnected-(Core1-PA14-Pad36)") (class "Default")
      (node (ref "Core1") (pin "36") (pinfunction "PA14_36") (pintype "passive"))
    )
    (net (code "94") (name "unconnected-(Core1-PA15-Pad35)") (class "Default")
      (node (ref "Core1") (pin "35") (pinfunction "PA15_35") (pintype "passive"))
    )
    (net (code "95") (name "unconnected-(Core1-PB0-Pad21)") (class "Default")
      (node (ref "Core1") (pin "21") (pinfunction "PB0_21") (pintype "passive"))
    )
    (net (code "96") (name "unconnected-(Core1-PB1-Pad22)") (class "Default")
      (node (ref "Core1") (pin "22") (pinfunction "PB1_22") (pintype "passive"))
    )
    (net (code "97") (name "unconnected-(Core1-PB2-Pad23)") (class "Default")
      (node (ref "Core1") (pin "23") (pinfunction "PB2_23") (pintype "passive"))
    )
    (net (code "98") (name "unconnected-(Core1-PB3-Pad32)") (class "Default")
      (node (ref "Core1") (pin "32") (pinfunction "PB3_32") (pintype "passive"))
    )
    (net (code "99") (name "unconnected-(Core1-PB4-Pad31)") (class "Default")
      (node (ref "Core1") (pin "31") (pinfunction "PB4_31") (pintype "passive"))
    )
    (net (code "100") (name "unconnected-(Core1-PB5-Pad30)") (class "Default")
      (node (ref "Core1") (pin "30") (pinfunction "PB5_30") (pintype "passive"))
    )
    (net (code "101") (name "unconnected-(Core1-PB6-Pad29)") (class "Default")
      (node (ref "Core1") (pin "29") (pinfunction "PB6_29") (pintype "passive"))
    )
    (net (code "102") (name "unconnected-(Core1-PB7-Pad28)") (class "Default")
      (node (ref "Core1") (pin "28") (pinfunction "PB7_28") (pintype "passive"))
    )
    (net (code "103") (name "unconnected-(Core1-PB8-Pad27)") (class "Default")
      (node (ref "Core1") (pin "27") (pinfunction "PB8_27") (pintype "passive"))
    )
    (net (code "104") (name "unconnected-(Core1-PB9-Pad26)") (class "Default")
      (node (ref "Core1") (pin "26") (pinfunction "PB9_26") (pintype "passive"))
    )
    (net (code "105") (name "unconnected-(Core1-PC2-Pad8)") (class "Default")
      (node (ref "Core1") (pin "8") (pinfunction "PC2_8") (pintype "passive"))
    )
    (net (code "106") (name "unconnected-(Core1-PC3-Pad9)") (class "Default")
      (node (ref "Core1") (pin "9") (pinfunction "PC3_9") (pintype "passive"))
    )
    (net (code "107") (name "unconnected-(Core1-PC4-Pad19)") (class "Default")
      (node (ref "Core1") (pin "19") (pinfunction "PC4_19") (pintype "passive"))
    )
    (net (code "108") (name "unconnected-(Core1-PC5-Pad20)") (class "Default")
      (node (ref "Core1") (pin "20") (pinfunction "PC5_20") (pintype "passive"))
    )
    (net (code "109") (name "unconnected-(Core1-PC6-Pad46)") (class "Default")
      (node (ref "Core1") (pin "46") (pinfunction "PC6_46") (pintype "passive"))
    )
    (net (code "110") (name "unconnected-(Core1-PC7-Pad45)") (class "Default")
      (node (ref "Core1") (pin "45") (pinfunction "PC7_45") (pintype "passive"))
    )
    (net (code "111") (name "unconnected-(Core1-PC8-Pad44)") (class "Default")
      (node (ref "Core1") (pin "44") (pinfunction "PC8_44") (pintype "passive"))
    )
    (net (code "112") (name "unconnected-(Core1-PC9-Pad43)") (class "Default")
      (node (ref "Core1") (pin "43") (pinfunction "PC9_43") (pintype "passive"))
    )
    (net (code "113") (name "unconnected-(Core1-PC10-Pad34)") (class "Default")
      (node (ref "Core1") (pin "34") (pinfunction "PC10_34") (pintype "passive"))
    )
    (net (code "114") (name "unconnected-(Core1-PD2-Pad33)") (class "Default")
      (node (ref "Core1") (pin "33") (pinfunction "PD2_33") (pintype "passive"))
    )
    (net (code "115") (name "unconnected-(TJA1-Vref-Pad5)") (class "Default")
      (node (ref "TJA1") (pin "5") (pinfunction "Vref_5") (pintype "passive"))
    )
    (net (code "116") (name "unconnected-(step_down1-GND-Pad2)") (class "Default")
      (node (ref "step_down1") (pin "2") (pinfunction "GND_2") (pintype "passive"))
    )
    (net (code "117") (name "unconnected-(step_down1-NC-Pad3)") (class "Default")
      (node (ref "step_down1") (pin "3") (pinfunction "NC_3") (pintype "passive"))
    )
    (net (code "118") (name "unconnected-(step_down1-VIN-Pad4)") (class "Default")
      (node (ref "step_down1") (pin "4") (pinfunction "VIN_4") (pintype "passive"))
    )
    (net (code "119") (name "unconnected-(step_down1-VUP-Pad8)") (class "Default")
      (node (ref "step_down1") (pin "8") (pinfunction "VUP_8") (pintype "passive"))
    )
    (net (code "120") (name "unconnected-(step_down1-VUP-Pad9)") (class "Default")
      (node (ref "step_down1") (pin "9") (pinfunction "VUP_9") (pintype "passive"))
    )
  )
)
